# eDP.net
KiCad netlist of a schematic drawn in Altium Designer
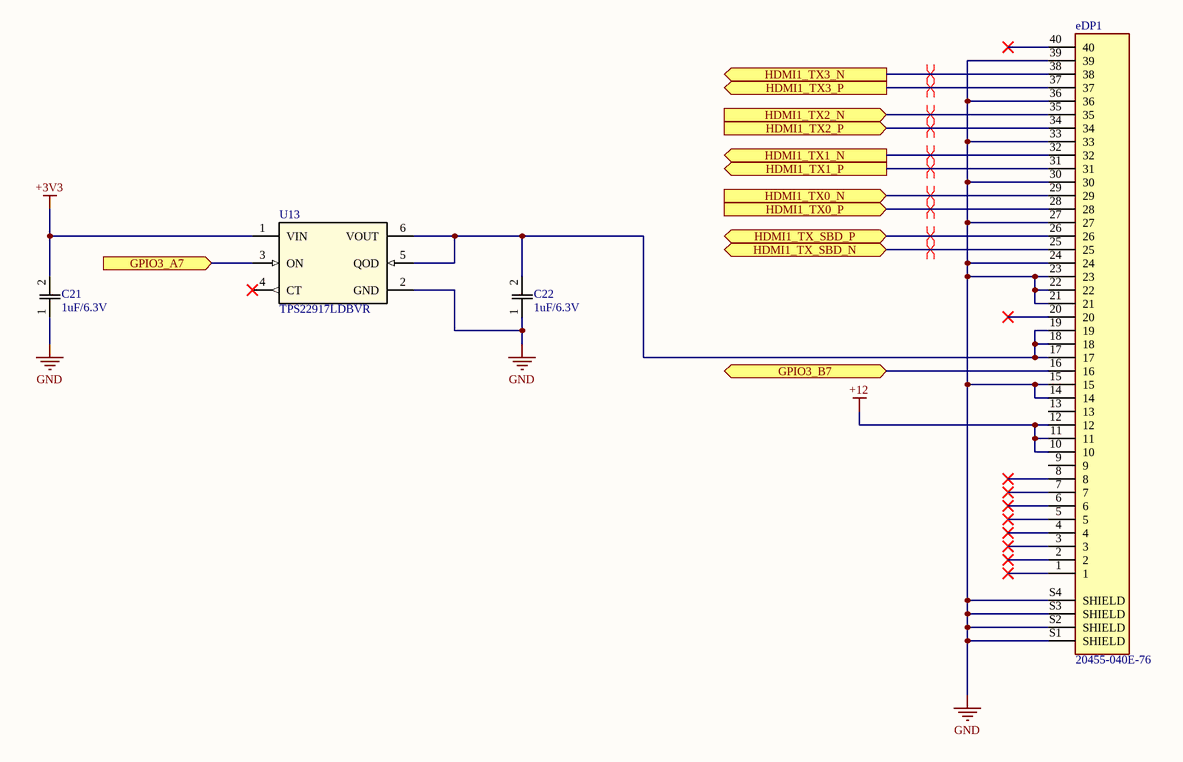
[diagram p0: eDP.SchDoc]

(export (version "E")
  (design (tool "Eeschema 10.0.6"))
  (components
    (comp (ref "C21")
      (value "1uF/6.3V")
      (footprint "C0805")
      (description "1 uF, 6.3 V, ± 10%, X7R, 0805 [2012 Metric] Multilayer Ceramic Capacitor,")
      (fields
        (field (name "MANUFACTURER_PART_NUMBER") "C0805C105K9RACTU")
        (field (name "MOUSER PART NUMBER") "80-C0805C105K9R")
      )
      (libsource (lib "DARKYDEN") (part "C0805C105K9RACTU"))
    )
    (comp (ref "C22")
      (value "1uF/6.3V")
      (footprint "C0805")
      (description "1 uF, 6.3 V, ± 10%, X7R, 0805 [2012 Metric] Multilayer Ceramic Capacitor,")
      (fields
        (field (name "MANUFACTURER_PART_NUMBER") "C0805C105K9RACTU")
        (field (name "MOUSER PART NUMBER") "80-C0805C105K9R")
      )
      (libsource (lib "DARKYDEN") (part "C0805C105K9RACTU"))
    )
    (comp (ref "eDP1")
      (value "20455-040E-76")
      (footprint "IPEX_20455-040E-76")
      (description "Conn Wire to Board RCP 40 POS 0.5mm Solder RA Side Entry SMDCABLINE® T/R")
      (fields (field (name "MANUFACTURER") "I-PEX"))
      (libsource (lib "20455-040E-76") (part "20455-040E-76"))
    )
    (comp (ref "U13")
      (value "TPS22917LDBVR")
      (footprint "DBV0006_L")
      (fields (field (name "MANUFACTURER") "Texas Instruments"))
      (libsource (lib "TPS22917LDBVR") (part "TPS22917LDBVR"))
    )
  )
  (nets
    (net (code "1") (name "+3V3") (class "Default")
      (node (ref "C21") (pin "2") (pinfunction "2_2") (pintype "passive"))
      (node (ref "U13") (pin "1") (pinfunction "VIN_1") (pintype "power_in"))
    )
    (net (code "2") (name "+12") (class "Default")
      (node (ref "eDP1") (pin "10") (pinfunction "10_10") (pintype "passive"))
      (node (ref "eDP1") (pin "11") (pinfunction "11_11") (pintype "passive"))
      (node (ref "eDP1") (pin "12") (pinfunction "12_12") (pintype "passive"))
    )
    (net (code "3") (name "/GPIO3_A7") (class "Default")
      (node (ref "U13") (pin "3") (pinfunction "ON_3") (pintype "input"))
    )
    (net (code "4") (name "/GPIO3_B7") (class "Default")
      (node (ref "eDP1") (pin "16") (pinfunction "16_16") (pintype "passive"))
    )
    (net (code "5") (name "/HDMI1_TX0_N") (class "Default")
      (node (ref "eDP1") (pin "29") (pinfunction "29_29") (pintype "passive"))
    )
    (net (code "6") (name "/HDMI1_TX0_P") (class "Default")
      (node (ref "eDP1") (pin "28") (pinfunction "28_28") (pintype "passive"))
    )
    (net (code "7") (name "/HDMI1_TX1_N") (class "Default")
      (node (ref "eDP1") (pin "32") (pinfunction "32_32") (pintype "passive"))
    )
    (net (code "8") (name "/HDMI1_TX1_P") (class "Default")
      (node (ref "eDP1") (pin "31") (pinfunction "31_31") (pintype "passive"))
    )
    (net (code "9") (name "/HDMI1_TX2_N") (class "Default")
      (node (ref "eDP1") (pin "35") (pinfunction "35_35") (pintype "passive"))
    )
    (net (code "10") (name "/HDMI1_TX2_P") (class "Default")
      (node (ref "eDP1") (pin "34") (pinfunction "34_34") (pintype "passive"))
    )
    (net (code "11") (name "/HDMI1_TX3_N") (class "Default")
      (node (ref "eDP1") (pin "38") (pinfunction "38_38") (pintype "passive"))
    )
    (net (code "12") (name "/HDMI1_TX3_P") (class "Default")
      (node (ref "eDP1") (pin "37") (pinfunction "37_37") (pintype "passive"))
    )
    (net (code "13") (name "/HDMI1_TX_SBD_N") (class "Default")
      (node (ref "eDP1") (pin "25") (pinfunction "25_25") (pintype "passive"))
    )
    (net (code "14") (name "/HDMI1_TX_SBD_P") (class "Default")
      (node (ref "eDP1") (pin "26") (pinfunction "26_26") (pintype "passive"))
    )
    (net (code "15") (name "GND") (class "Default")
      (node (ref "C21") (pin "1") (pinfunction "1_1") (pintype "passive"))
      (node (ref "C22") (pin "1") (pinfunction "1_1") (pintype "passive"))
      (node (ref "U13") (pin "2") (pinfunction "GND_2") (pintype "passive"))
      (node (ref "eDP1") (pin "14") (pinfunction "14_14") (pintype "passive"))
      (node (ref "eDP1") (pin "15") (pinfunction "15_15") (pintype "passive"))
      (node (ref "eDP1") (pin "21") (pinfunction "21_21") (pintype "passive"))
      (node (ref "eDP1") (pin "22") (pinfunction "22_22") (pintype "passive"))
      (node (ref "eDP1") (pin "23") (pinfunction "23_23") (pintype "passive"))
      (node (ref "eDP1") (pin "24") (pinfunction "24_24") (pintype "passive"))
      (node (ref "eDP1") (pin "27") (pinfunction "27_27") (pintype "passive"))
      (node (ref "eDP1") (pin "30") (pinfunction "30_30") (pintype "passive"))
      (node (ref "eDP1") (pin "33") (pinfunction "33_33") (pintype "passive"))
      (node (ref "eDP1") (pin "36") (pinfunction "36_36") (pintype "passive"))
      (node (ref "eDP1") (pin "39") (pinfunction "39_39") (pintype "passive"))
      (node (ref "eDP1") (pin "S1") (pinfunction "SHIELD_S1") (pintype "passive"))
      (node (ref "eDP1") (pin "S2") (pinfunction "SHIELD_S2") (pintype "passive"))
      (node (ref "eDP1") (pin "S3") (pinfunction "SHIELD_S3") (pintype "passive"))
      (node (ref "eDP1") (pin "S4") (pinfunction "SHIELD_S4") (pintype "passive"))
    )
    (net (code "16") (name "Net-(U13-QOD)") (class "Default")
      (node (ref "C22") (pin "2") (pinfunction "2_2") (pintype "passive"))
      (node (ref "U13") (pin "5") (pinfunction "QOD_5") (pintype "input"))
      (node (ref "U13") (pin "6") (pinfunction "VOUT_6") (pintype "power_in"))
      (node (ref "eDP1") (pin "17") (pinfunction "17_17") (pintype "passive"))
      (node (ref "eDP1") (pin "18") (pinfunction "18_18") (pintype "passive"))
      (node (ref "eDP1") (pin "19") (pinfunction "19_19") (pintype "passive"))
    )
    (net (code "17") (name "unconnected-(U13-CT-Pad4)") (class "Default")
      (node (ref "U13") (pin "4") (pinfunction "CT_4") (pintype "output+no_connect"))
    )
    (net (code "18") (name "unconnected-(eDP1-Pad1)") (class "Default")
      (node (ref "eDP1") (pin "1") (pinfunction "1_1") (pintype "passive+no_connect"))
    )
    (net (code "19") (name "unconnected-(eDP1-Pad2)") (class "Default")
      (node (ref "eDP1") (pin "2") (pinfunction "2_2") (pintype "passive+no_connect"))
    )
    (net (code "20") (name "unconnected-(eDP1-Pad3)") (class "Default")
      (node (ref "eDP1") (pin "3") (pinfunction "3_3") (pintype "passive+no_connect"))
    )
    (net (code "21") (name "unconnected-(eDP1-Pad4)") (class "Default")
      (node (ref "eDP1") (pin "4") (pinfunction "4_4") (pintype "passive+no_connect"))
    )
    (net (code "22") (name "unconnected-(eDP1-Pad5)") (class "Default")
      (node (ref "eDP1") (pin "5") (pinfunction "5_5") (pintype "passive+no_connect"))
    )
    (net (code "23") (name "unconnected-(eDP1-Pad6)") (class "Default")
      (node (ref "eDP1") (pin "6") (pinfunction "6_6") (pintype "passive+no_connect"))
    )
    (net (code "24") (name "unconnected-(eDP1-Pad7)") (class "Default")
      (node (ref "eDP1") (pin "7") (pinfunction "7_7") (pintype "passive+no_connect"))
    )
    (net (code "25") (name "unconnected-(eDP1-Pad8)") (class "Default")
      (node (ref "eDP1") (pin "8") (pinfunction "8_8") (pintype "passive+no_connect"))
    )
    (net (code "26") (name "unconnected-(eDP1-Pad9)") (class "Default")
      (node (ref "eDP1") (pin "9") (pinfunction "9_9") (pintype "passive"))
    )
    (net (code "27") (name "unconnected-(eDP1-Pad13)") (class "Default")
      (node (ref "eDP1") (pin "13") (pinfunction "13_13") (pintype "passive"))
    )
    (net (code "28") (name "unconnected-(eDP1-Pad20)") (class "Default")
      (node (ref "eDP1") (pin "20") (pinfunction "20_20") (pintype "passive+no_connect"))
    )
    (net (code "29") (name "unconnected-(eDP1-Pad40)") (class "Default")
      (node (ref "eDP1") (pin "40") (pinfunction "40_40") (pintype "passive+no_connect"))
    )
  )
)
